# button_board_v0_2.net
KiCad netlist of a schematic drawn in EAGLE
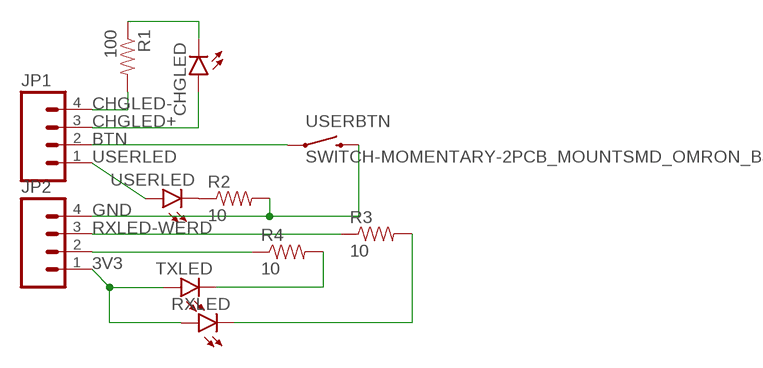
[diagram p0: schematic, sheet 1]

(export (version "E")
  (design (tool "Eeschema 10.0.6"))
  (components
    (comp (ref "CHGLED")
      (value "LED-FKIT-1206")
      (footprint "eagle-import:FKIT-LED-1206")
      (libsource (lib "eagle-import") (part "LED-FKIT-1206"))
    )
    (comp (ref "JP1")
      (value "M04PTH")
      (footprint "eagle-import:1X04")
      (libsource (lib "eagle-import") (part "M04PTH"))
    )
    (comp (ref "JP2")
      (value "M04PTH")
      (footprint "eagle-import:1X04")
      (libsource (lib "eagle-import") (part "M04PTH"))
    )
    (comp (ref "R1")
      (value "100")
      (footprint "eagle-import:0603-RES")
      (libsource (lib "eagle-import") (part "RESISTOR0603-RES"))
    )
    (comp (ref "R2")
      (value "10")
      (footprint "eagle-import:0603-RES")
      (libsource (lib "eagle-import") (part "RESISTOR0603-RES"))
    )
    (comp (ref "R3")
      (value "10")
      (footprint "eagle-import:0603-RES")
      (libsource (lib "eagle-import") (part "RESISTOR0603-RES"))
    )
    (comp (ref "R4")
      (value "10")
      (footprint "eagle-import:0603-RES")
      (libsource (lib "eagle-import") (part "RESISTOR0603-RES"))
    )
    (comp (ref "RXLED")
      (value "LED-FKIT-1206")
      (footprint "eagle-import:FKIT-LED-1206")
      (libsource (lib "eagle-import") (part "LED-FKIT-1206"))
    )
    (comp (ref "TXLED")
      (value "LED-FKIT-1206")
      (footprint "eagle-import:FKIT-LED-1206")
      (libsource (lib "eagle-import") (part "LED-FKIT-1206"))
    )
    (comp (ref "USERBTN")
      (value "SWITCH-MOMENTARY-2PCB_MOUNTSMD_OMRON_B3S_100X")
      (footprint "eagle-import:TACTILE_SWITCH_LARGE")
      (libsource (lib "eagle-import") (part "SWITCH-MOMENTARY-2SMD_OMRON_B3S_100XPCB_MOUNT"))
    )
    (comp (ref "USERLED")
      (value "LED-FKIT-1206")
      (footprint "eagle-import:FKIT-LED-1206")
      (libsource (lib "eagle-import") (part "LED-FKIT-1206"))
    )
  )
  (nets
    (net (code "1") (name "/3V3") (class "Default")
      (node (ref "JP2") (pin "1") (pinfunction "1_1") (pintype "passive"))
      (node (ref "RXLED") (pin "A") (pinfunction "A_A") (pintype "passive"))
      (node (ref "TXLED") (pin "A") (pinfunction "A_A") (pintype "passive"))
    )
    (net (code "2") (name "/BTN") (class "Default")
      (node (ref "JP1") (pin "2") (pinfunction "2_2") (pintype "passive"))
      (node (ref "USERBTN") (pin "1") (pinfunction "1_1") (pintype "passive"))
      (node (ref "USERBTN") (pin "2") (pinfunction "1_2") (pintype "passive"))
    )
    (net (code "3") (name "/CHGLED+") (class "Default")
      (node (ref "CHGLED") (pin "A") (pinfunction "A_A") (pintype "passive"))
      (node (ref "JP1") (pin "3") (pinfunction "3_3") (pintype "passive"))
    )
    (net (code "4") (name "/CHGLED-") (class "Default")
      (node (ref "JP1") (pin "4") (pinfunction "4_4") (pintype "passive"))
      (node (ref "R1") (pin "2") (pinfunction "2_2") (pintype "passive"))
    )
    (net (code "5") (name "/GND") (class "Default")
      (node (ref "JP2") (pin "4") (pinfunction "4_4") (pintype "passive"))
      (node (ref "R2") (pin "2") (pinfunction "2_2") (pintype "passive"))
      (node (ref "USERBTN") (pin "3") (pinfunction "2_3") (pintype "passive"))
      (node (ref "USERBTN") (pin "4") (pinfunction "2_4") (pintype "passive"))
    )
    (net (code "6") (name "/RXLED-WERD") (class "Default")
      (node (ref "R3") (pin "2") (pinfunction "2_2") (pintype "passive"))
      (node (ref "RXLED") (pin "C") (pinfunction "C_C") (pintype "passive"))
    )
    (net (code "7") (name "/USERLED") (class "Default")
      (node (ref "JP1") (pin "1") (pinfunction "1_1") (pintype "passive"))
      (node (ref "USERLED") (pin "A") (pinfunction "A_A") (pintype "passive"))
    )
    (net (code "8") (name "Net-(CHGLED-PadC)") (class "Default")
      (node (ref "CHGLED") (pin "C") (pinfunction "C_C") (pintype "passive"))
      (node (ref "R1") (pin "1") (pinfunction "1_1") (pintype "passive"))
    )
    (net (code "9") (name "Net-(JP2-Pad2)") (class "Default")
      (node (ref "JP2") (pin "2") (pinfunction "2_2") (pintype "passive"))
      (node (ref "R4") (pin "1") (pinfunction "1_1") (pintype "passive"))
    )
    (net (code "10") (name "Net-(JP2-Pad3)") (class "Default")
      (node (ref "JP2") (pin "3") (pinfunction "3_3") (pintype "passive"))
      (node (ref "R3") (pin "1") (pinfunction "1_1") (pintype "passive"))
    )
    (net (code "11") (name "Net-(R2-Pad1)") (class "Default")
      (node (ref "R2") (pin "1") (pinfunction "1_1") (pintype "passive"))
      (node (ref "USERLED") (pin "C") (pinfunction "C_C") (pintype "passive"))
    )
    (net (code "12") (name "Net-(R4-Pad2)") (class "Default")
      (node (ref "R4") (pin "2") (pinfunction "2_2") (pintype "passive"))
      (node (ref "TXLED") (pin "C") (pinfunction "C_C") (pintype "passive"))
    )
  )
)
